# Sheet2.net
KiCad netlist of a schematic drawn in Altium Designer
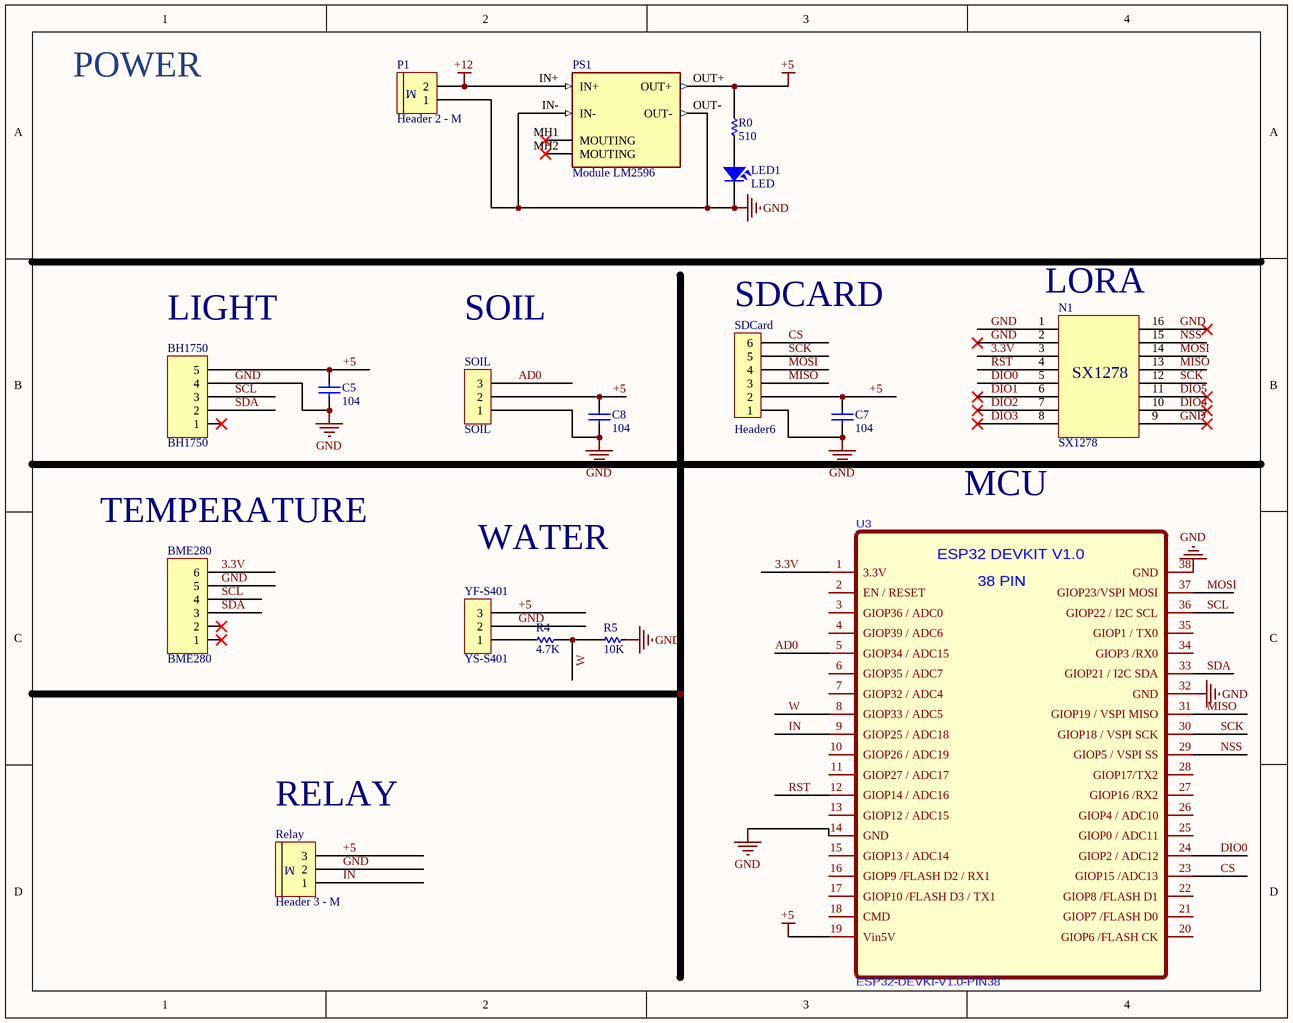
[diagram p0: Sheet2.SchDoc]

(export (version "E")
  (design (tool "Eeschema 10.0.6"))
  (components
    (comp (ref "BH1750")
      (value "BH1750")
      (footprint "JP5-C1T")
      (description "WR-PHD 2.54 mm Angled Socket Header")
      (fields
        (field (name "MANUFACTURER") "Würth Elektronik eiSos GmbH")
        (field (name "PARTNO") "613005143121")
        (field (name "CREATED BY") "Karrer Zheng")
      )
      (libsource (lib "Altium Library") (part "JP5"))
    )
    (comp (ref "BME280")
      (value "BME280")
      (footprint "JP6-C1T")
      (description "WR-PHD 2.54 mm Angled Socket Header")
      (fields
        (field (name "MANUFACTURER") "Würth Elektronik eiSos GmbH")
        (field (name "PARTNO") "613006143121")
        (field (name "CREATED BY") "Karrer Zheng")
      )
      (libsource (lib "Altium Library") (part "JP6"))
    )
    (comp (ref "C5")
      (value "104")
      (footprint "Tu-pico")
      (description "Capacitor")
      (fields (field (name "Comment") "Capacitor Ceramic") (field (name "PUBLISHER") "Altium Limited"))
      (libsource (lib "My Library") (part "CapCeramic"))
    )
    (comp (ref "C7")
      (value "104")
      (footprint "Tu-pico")
      (description "Capacitor")
      (fields (field (name "Comment") "Capacitor Ceramic") (field (name "PUBLISHER") "Altium Limited"))
      (libsource (lib "My Library") (part "CapCeramic"))
    )
    (comp (ref "C8")
      (value "104")
      (footprint "Tu-pico")
      (description "Capacitor")
      (fields (field (name "Comment") "Capacitor Ceramic") (field (name "PUBLISHER") "Altium Limited"))
      (libsource (lib "My Library") (part "CapCeramic"))
    )
    (comp (ref "LED1")
      (value "LED")
      (footprint "LED-3")
      (description "LED Single colour Green and Red")
      (libsource (lib "My Library") (part "LED"))
    )
    (comp (ref "N1") (value "SX1278") (footprint "DIP16") (libsource (lib "TV") (part "SX1278")))
    (comp (ref "P1")
      (value "Header 2 - M")
      (footprint "Medium - Header 2")
      (description "Header, 2-Pin, Medium")
      (fields (field (name "PUBLISHER") "Altium Limited"))
      (libsource (lib "My Library (1)") (part "Header 2 - M"))
    )
    (comp (ref "PS1")
      (value "Module LM2596")
      (footprint "CONV_MC00100")
      (description "DC-DC LM2596 Step Down Adjustable Converter Power Supply Module 1.3V-35V")
      (fields (field (name "MF") "YKS") (field (name "MP") "MC00100"))
      (libsource (lib "LM2596") (part "MC00100"))
    )
    (comp (ref "R0")
      (value "510")
      (footprint "RES-1/2W")
      (description "Res")
      (fields
        (field (name "MANUFACTURER") "Generic Components")
        (field (name "PUBLISHER") "Altium Hobart Technology Centre")
      )
      (libsource (lib "Altium Library") (part "Res"))
    )
    (comp (ref "R4")
      (value "4.7K")
      (footprint "RES-1/2W")
      (description "Res")
      (fields
        (field (name "MANUFACTURER") "Generic Components")
        (field (name "PUBLISHER") "Altium Hobart Technology Centre")
      )
      (libsource (lib "Altium Library") (part "Res"))
    )
    (comp (ref "R5")
      (value "10K")
      (footprint "RES-1/2W")
      (description "Res")
      (fields
        (field (name "MANUFACTURER") "Generic Components")
        (field (name "PUBLISHER") "Altium Hobart Technology Centre")
      )
      (libsource (lib "Altium Library") (part "Res"))
    )
    (comp (ref "Relay")
      (value "Header 3 - M")
      (footprint "Medium - Header 3")
      (description "Header, 3-Pin, Medium")
      (fields (field (name "PUBLISHER") "Altium Limited"))
      (libsource (lib "Devzone_SCHLib") (part "Header 3 - M"))
    )
    (comp (ref "SDCard")
      (value "Header6")
      (footprint "HDR6")
      (description "Header IDC, 6 x 1 Pin Vertical 2.54mm Pitch (Non-Boxed, Male)")
      (fields
        (field (name "MANUFACTURER") "Würth Elektronik eiSos GmbH")
        (field (name "PARTNO") "613002143121")
        (field (name "CREATED BY") "Karrer Zheng")
      )
      (libsource (lib "My Library") (part "Header6"))
    )
    (comp (ref "SOIL")
      (value "SOIL")
      (footprint "JP3-D1T")
      (description "WR-PHD 2.54 mm Angled Socket Header")
      (fields
        (field (name "MANUFACTURER") "Würth Elektronik eiSos GmbH")
        (field (name "PARTNO") "613003143121")
        (field (name "CREATED BY") "Karrer Zheng")
      )
      (libsource (lib "Altium Library") (part "JP3"))
    )
    (comp (ref "U3")
      (value "ESP32-DEVKI-V1.0-PIN38")
      (footprint "ESP32-DEVKIT-V1.0-38PIN")
      (libsource (lib "My Library") (part "ESP32-DEVKI-V1.0-PIN38"))
    )
    (comp (ref "YF-S401")
      (value "YS-S401")
      (footprint "JP3-D1T")
      (description "WR-PHD 2.54 mm Angled Socket Header")
      (fields
        (field (name "MANUFACTURER") "Würth Elektronik eiSos GmbH")
        (field (name "PARTNO") "613003143121")
        (field (name "CREATED BY") "Karrer Zheng")
      )
      (libsource (lib "Altium Library") (part "JP3"))
    )
  )
  (nets
    (net (code "1") (name "+5") (class "Default")
      (node (ref "BH1750") (pin "5") (pinfunction "5_5") (pintype "passive"))
      (node (ref "C5") (pin "2") (pinfunction "2_2") (pintype "passive"))
      (node (ref "C7") (pin "2") (pinfunction "2_2") (pintype "passive"))
      (node (ref "C8") (pin "2") (pinfunction "2_2") (pintype "passive"))
      (node (ref "PS1") (pin "OUT+") (pinfunction "OUT+_OUT+") (pintype "output"))
      (node (ref "R0") (pin "1") (pinfunction "1_1") (pintype "passive"))
      (node (ref "Relay") (pin "3") (pinfunction "3_3") (pintype "passive"))
      (node (ref "SDCard") (pin "2") (pinfunction "2_2") (pintype "passive"))
      (node (ref "SOIL") (pin "2") (pinfunction "2_2") (pintype "passive"))
      (node (ref "U3") (pin "19") (pinfunction "Vin5V_19") (pintype "passive"))
      (node (ref "YF-S401") (pin "3") (pinfunction "3_3") (pintype "passive"))
    )
    (net (code "2") (name "+12") (class "Default")
      (node (ref "P1") (pin "2") (pinfunction "2_2") (pintype "passive"))
      (node (ref "PS1") (pin "IN+") (pinfunction "IN+_IN+") (pintype "input"))
    )
    (net (code "3") (name "/3.3V") (class "Default")
      (node (ref "BME280") (pin "6") (pinfunction "6_6") (pintype "passive"))
      (node (ref "N1") (pin "3") (pinfunction "3_3") (pintype "passive"))
      (node (ref "U3") (pin "1") (pinfunction "3.3V_1") (pintype "passive"))
    )
    (net (code "4") (name "/AD0") (class "Default")
      (node (ref "SOIL") (pin "3") (pinfunction "3_3") (pintype "passive"))
      (node (ref "U3") (pin "5") (pinfunction "GIOP34_/_ADC15_5") (pintype "passive"))
    )
    (net (code "5") (name "/CS") (class "Default")
      (node (ref "SDCard") (pin "6") (pinfunction "6_6") (pintype "passive"))
      (node (ref "U3") (pin "23") (pinfunction "GIOP15_/ADC13_23") (pintype "passive"))
    )
    (net (code "6") (name "/DIO0") (class "Default")
      (node (ref "N1") (pin "5") (pinfunction "5_5") (pintype "passive"))
      (node (ref "U3") (pin "24") (pinfunction "GIOP2_/_ADC12_24") (pintype "passive"))
    )
    (net (code "7") (name "/DIO1") (class "Default")
      (node (ref "N1") (pin "6") (pinfunction "6_6") (pintype "passive+no_connect"))
    )
    (net (code "8") (name "/DIO2") (class "Default")
      (node (ref "N1") (pin "7") (pinfunction "7_7") (pintype "passive+no_connect"))
    )
    (net (code "9") (name "/DIO3") (class "Default")
      (node (ref "N1") (pin "8") (pinfunction "8_8") (pintype "passive+no_connect"))
    )
    (net (code "10") (name "/DIO4") (class "Default")
      (node (ref "N1") (pin "10") (pinfunction "10_10") (pintype "passive+no_connect"))
    )
    (net (code "11") (name "/DIO5") (class "Default")
      (node (ref "N1") (pin "11") (pinfunction "11_11") (pintype "passive+no_connect"))
    )
    (net (code "12") (name "/IN") (class "Default")
      (node (ref "Relay") (pin "1") (pinfunction "1_1") (pintype "passive"))
      (node (ref "U3") (pin "9") (pinfunction "GIOP25_/_ADC18_9") (pintype "passive"))
    )
    (net (code "13") (name "/MISO") (class "Default")
      (node (ref "N1") (pin "13") (pinfunction "13_13") (pintype "passive"))
      (node (ref "SDCard") (pin "3") (pinfunction "3_3") (pintype "passive"))
      (node (ref "U3") (pin "31") (pinfunction "GIOP19_/_VSPI_MISO_31") (pintype "passive"))
    )
    (net (code "14") (name "/MOSI") (class "Default")
      (node (ref "N1") (pin "14") (pinfunction "14_14") (pintype "passive"))
      (node (ref "SDCard") (pin "4") (pinfunction "4_4") (pintype "passive"))
      (node (ref "U3") (pin "37") (pinfunction "GIOP23/VSPI_MOSI_37") (pintype "passive"))
    )
    (net (code "15") (name "/NSS") (class "Default")
      (node (ref "N1") (pin "15") (pinfunction "15_15") (pintype "passive"))
      (node (ref "U3") (pin "29") (pinfunction "GIOP5_/_VSPI_SS_29") (pintype "passive"))
    )
    (net (code "16") (name "/RST") (class "Default")
      (node (ref "N1") (pin "4") (pinfunction "4_4") (pintype "passive"))
      (node (ref "U3") (pin "12") (pinfunction "GIOP14_/_ADC16_12") (pintype "passive"))
    )
    (net (code "17") (name "/SCK") (class "Default")
      (node (ref "N1") (pin "12") (pinfunction "12_12") (pintype "passive"))
      (node (ref "SDCard") (pin "5") (pinfunction "5_5") (pintype "passive"))
      (node (ref "U3") (pin "30") (pinfunction "GIOP18_/_VSPI_SCK_30") (pintype "passive"))
    )
    (net (code "18") (name "/SCL") (class "Default")
      (node (ref "BH1750") (pin "3") (pinfunction "3_3") (pintype "passive"))
      (node (ref "BME280") (pin "4") (pinfunction "4_4") (pintype "passive"))
      (node (ref "U3") (pin "36") (pinfunction "GIOP22_/_I2C_SCL_36") (pintype "passive"))
    )
    (net (code "19") (name "/SDA") (class "Default")
      (node (ref "BH1750") (pin "2") (pinfunction "2_2") (pintype "passive"))
      (node (ref "BME280") (pin "3") (pinfunction "3_3") (pintype "passive"))
      (node (ref "U3") (pin "33") (pinfunction "GIOP21_/_I2C_SDA_33") (pintype "passive"))
    )
    (net (code "20") (name "/W") (class "Default")
      (node (ref "R4") (pin "1") (pinfunction "1_1") (pintype "passive"))
      (node (ref "R5") (pin "1") (pinfunction "1_1") (pintype "passive"))
      (node (ref "U3") (pin "8") (pinfunction "GIOP33_/_ADC5_8") (pintype "passive"))
    )
    (net (code "21") (name "GND") (class "Default")
      (node (ref "BH1750") (pin "4") (pinfunction "4_4") (pintype "passive"))
      (node (ref "BME280") (pin "5") (pinfunction "5_5") (pintype "passive"))
      (node (ref "C5") (pin "1") (pinfunction "1_1") (pintype "passive"))
      (node (ref "C7") (pin "1") (pinfunction "1_1") (pintype "passive"))
      (node (ref "C8") (pin "1") (pinfunction "1_1") (pintype "passive"))
      (node (ref "LED1") (pin "2") (pinfunction "2_2") (pintype "passive"))
      (node (ref "N1") (pin "1") (pinfunction "1_1") (pintype "passive"))
      (node (ref "N1") (pin "16") (pinfunction "16_16") (pintype "passive"))
      (node (ref "N1") (pin "2") (pinfunction "2_2") (pintype "passive"))
      (node (ref "N1") (pin "9") (pinfunction "9_9") (pintype "passive"))
      (node (ref "P1") (pin "1") (pinfunction "1_1") (pintype "passive"))
      (node (ref "PS1") (pin "IN-") (pinfunction "IN-_IN-") (pintype "input"))
      (node (ref "PS1") (pin "OUT-") (pinfunction "OUT-_OUT-") (pintype "output"))
      (node (ref "R5") (pin "2") (pinfunction "2_2") (pintype "passive"))
      (node (ref "Relay") (pin "2") (pinfunction "2_2") (pintype "passive"))
      (node (ref "SDCard") (pin "1") (pinfunction "1_1") (pintype "passive"))
      (node (ref "SOIL") (pin "1") (pinfunction "1_1") (pintype "passive"))
      (node (ref "U3") (pin "14") (pinfunction "GND_14") (pintype "passive"))
      (node (ref "U3") (pin "32") (pinfunction "GND_32") (pintype "passive"))
      (node (ref "U3") (pin "38") (pinfunction "GND_38") (pintype "passive"))
      (node (ref "YF-S401") (pin "2") (pinfunction "2_2") (pintype "passive"))
    )
    (net (code "22") (name "Net-(LED1-Pad1)") (class "Default")
      (node (ref "LED1") (pin "1") (pinfunction "1_1") (pintype "passive"))
      (node (ref "R0") (pin "2") (pinfunction "2_2") (pintype "passive"))
    )
    (net (code "23") (name "Net-(R4-Pad2)") (class "Default")
      (node (ref "R4") (pin "2") (pinfunction "2_2") (pintype "passive"))
      (node (ref "YF-S401") (pin "1") (pinfunction "1_1") (pintype "passive"))
    )
    (net (code "24") (name "unconnected-(BH1750-Pad1)") (class "Default")
      (node (ref "BH1750") (pin "1") (pinfunction "1_1") (pintype "passive+no_connect"))
    )
    (net (code "25") (name "unconnected-(BME280-Pad1)") (class "Default")
      (node (ref "BME280") (pin "1") (pinfunction "1_1") (pintype "passive+no_connect"))
    )
    (net (code "26") (name "unconnected-(BME280-Pad2)") (class "Default")
      (node (ref "BME280") (pin "2") (pinfunction "2_2") (pintype "passive+no_connect"))
    )
    (net (code "27") (name "unconnected-(PS1-MOUTING-PadMH1)") (class "Default")
      (node (ref "PS1") (pin "MH1") (pinfunction "MOUTING_MH1") (pintype "passive+no_connect"))
    )
    (net (code "28") (name "unconnected-(PS1-MOUTING-PadMH2)") (class "Default")
      (node (ref "PS1") (pin "MH2") (pinfunction "MOUTING_MH2") (pintype "passive+no_connect"))
    )
    (net (code "29") (name "unconnected-(U3-CMD-Pad18)") (class "Default")
      (node (ref "U3") (pin "18") (pinfunction "CMD_18") (pintype "passive"))
    )
    (net (code "30") (name "unconnected-(U3-EN_{slash}_RESET-Pad2)") (class "Default")
      (node (ref "U3") (pin "2") (pinfunction "EN_/_RESET_2") (pintype "passive"))
    )
    (net (code "31") (name "unconnected-(U3-GIOP0_{slash}_ADC11-Pad25)") (class "Default")
      (node (ref "U3") (pin "25") (pinfunction "GIOP0_/_ADC11_25") (pintype "passive"))
    )
    (net (code "32") (name "unconnected-(U3-GIOP1_{slash}_TX0-Pad35)") (class "Default")
      (node (ref "U3") (pin "35") (pinfunction "GIOP1_/_TX0_35") (pintype "passive"))
    )
    (net (code "33") (name "unconnected-(U3-GIOP3_{slash}RX0-Pad34)") (class "Default")
      (node (ref "U3") (pin "34") (pinfunction "GIOP3_/RX0_34") (pintype "passive"))
    )
    (net (code "34") (name "unconnected-(U3-GIOP4_{slash}_ADC10-Pad26)") (class "Default")
      (node (ref "U3") (pin "26") (pinfunction "GIOP4_/_ADC10_26") (pintype "passive"))
    )
    (net (code "35") (name "unconnected-(U3-GIOP6_{slash}FLASH_CK-Pad20)") (class "Default")
      (node (ref "U3") (pin "20") (pinfunction "GIOP6_/FLASH_CK_20") (pintype "passive"))
    )
    (net (code "36") (name "unconnected-(U3-GIOP7_{slash}FLASH_D0-Pad21)") (class "Default")
      (node (ref "U3") (pin "21") (pinfunction "GIOP7_/FLASH_D0_21") (pintype "passive"))
    )
    (net (code "37") (name "unconnected-(U3-GIOP8_{slash}FLASH_D1-Pad22)") (class "Default")
      (node (ref "U3") (pin "22") (pinfunction "GIOP8_/FLASH_D1_22") (pintype "passive"))
    )
    (net (code "38") (name "unconnected-(U3-GIOP9_{slash}FLASH_D2_{slash}_RX1-Pad16)") (class "Default")
      (node (ref "U3") (pin "16") (pinfunction "GIOP9_/FLASH_D2_/_RX1_16") (pintype "passive"))
    )
    (net (code "39") (name "unconnected-(U3-GIOP10_{slash}FLASH_D3_{slash}_TX1-Pad17)") (class "Default")
      (node (ref "U3") (pin "17") (pinfunction "GIOP10_/FLASH_D3_/_TX1_17") (pintype "passive"))
    )
    (net (code "40") (name "unconnected-(U3-GIOP12_{slash}_ADC15-Pad13)") (class "Default")
      (node (ref "U3") (pin "13") (pinfunction "GIOP12_/_ADC15_13") (pintype "passive"))
    )
    (net (code "41") (name "unconnected-(U3-GIOP13_{slash}_ADC14-Pad15)") (class "Default")
      (node (ref "U3") (pin "15") (pinfunction "GIOP13_/_ADC14_15") (pintype "passive"))
    )
    (net (code "42") (name "unconnected-(U3-GIOP16_{slash}RX2-Pad27)") (class "Default")
      (node (ref "U3") (pin "27") (pinfunction "GIOP16_/RX2_27") (pintype "passive"))
    )
    (net (code "43") (name "unconnected-(U3-GIOP17{slash}TX2-Pad28)") (class "Default")
      (node (ref "U3") (pin "28") (pinfunction "GIOP17/TX2_28") (pintype "passive"))
    )
    (net (code "44") (name "unconnected-(U3-GIOP26_{slash}_ADC19-Pad10)") (class "Default")
      (node (ref "U3") (pin "10") (pinfunction "GIOP26_/_ADC19_10") (pintype "passive"))
    )
    (net (code "45") (name "unconnected-(U3-GIOP27_{slash}_ADC17-Pad11)") (class "Default")
      (node (ref "U3") (pin "11") (pinfunction "GIOP27_/_ADC17_11") (pintype "passive"))
    )
    (net (code "46") (name "unconnected-(U3-GIOP32_{slash}_ADC4-Pad7)") (class "Default")
      (node (ref "U3") (pin "7") (pinfunction "GIOP32_/_ADC4_7") (pintype "passive"))
    )
    (net (code "47") (name "unconnected-(U3-GIOP35_{slash}_ADC7-Pad6)") (class "Default")
      (node (ref "U3") (pin "6") (pinfunction "GIOP35_/_ADC7_6") (pintype "passive"))
    )
    (net (code "48") (name "unconnected-(U3-GIOP36_{slash}_ADC0-Pad3)") (class "Default")
      (node (ref "U3") (pin "3") (pinfunction "GIOP36_/_ADC0_3") (pintype "passive"))
    )
    (net (code "49") (name "unconnected-(U3-GIOP39_{slash}_ADC6-Pad4)") (class "Default")
      (node (ref "U3") (pin "4") (pinfunction "GIOP39_/_ADC6_4") (pintype "passive"))
    )
  )
)
